# GrblMainboard_-_v2_1.net
KiCad netlist of a schematic drawn in EAGLE
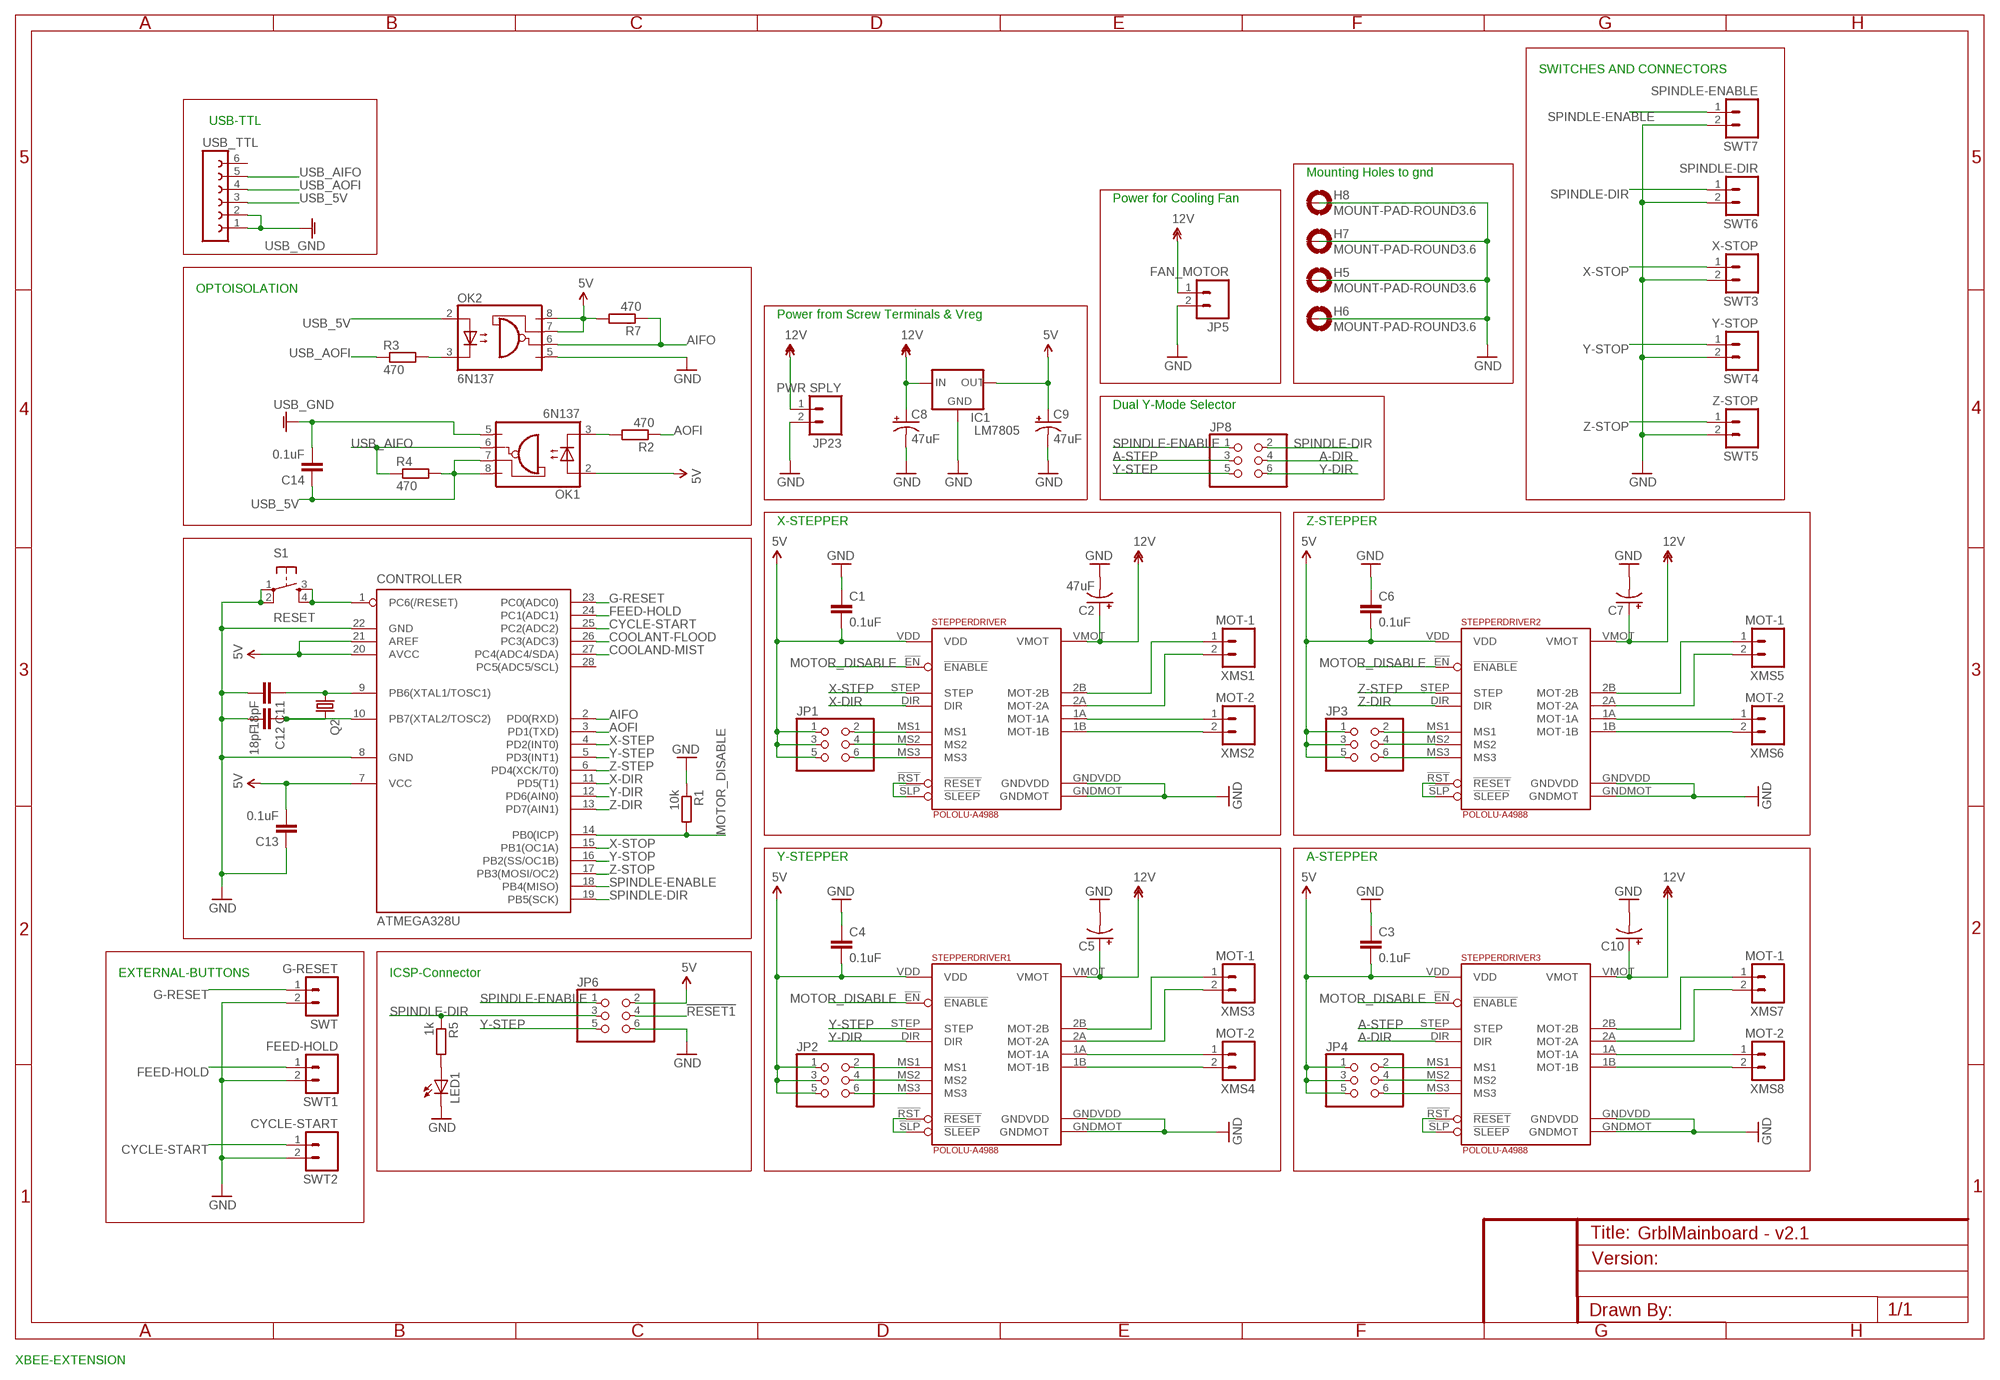
[diagram p0: schematic, sheet 1]

(export (version "E")
  (design (tool "Eeschema 10.0.6"))
  (components
    (comp (ref "ATMEGA328U")
      (value "CONTROLLER")
      (footprint "eagle-import:DIL28-3")
      (libsource (lib "eagle-import") (part "MEGA8-P"))
    )
    (comp (ref "C1")
      (value "0.1uF")
      (footprint "eagle-import:C025-025X050")
      (libsource (lib "eagle-import") (part "C-EU025-025X050"))
    )
    (comp (ref "C2")
      (value "47uF")
      (footprint "eagle-import:E2,5-6")
      (libsource (lib "eagle-import") (part "CPOL-USE2.5-6"))
    )
    (comp (ref "C3")
      (value "0.1uF")
      (footprint "eagle-import:C025-025X050")
      (libsource (lib "eagle-import") (part "C-EU025-025X050"))
    )
    (comp (ref "C4")
      (value "0.1uF")
      (footprint "eagle-import:C025-025X050")
      (libsource (lib "eagle-import") (part "C-EU025-025X050"))
    )
    (comp (ref "C5")
      (value "CPOL-USE2.5-6")
      (footprint "eagle-import:E2,5-6")
      (libsource (lib "eagle-import") (part "CPOL-USE2.5-6"))
    )
    (comp (ref "C6")
      (value "0.1uF")
      (footprint "eagle-import:C025-025X050")
      (libsource (lib "eagle-import") (part "C-EU025-025X050"))
    )
    (comp (ref "C7")
      (value "CPOL-USE2.5-6")
      (footprint "eagle-import:E2,5-6")
      (libsource (lib "eagle-import") (part "CPOL-USE2.5-6"))
    )
    (comp (ref "C8")
      (value "47uF")
      (footprint "eagle-import:E2,5-6")
      (libsource (lib "eagle-import") (part "CPOL-USE2.5-6"))
    )
    (comp (ref "C9")
      (value "47uF")
      (footprint "eagle-import:E2,5-6")
      (libsource (lib "eagle-import") (part "CPOL-USE2.5-6"))
    )
    (comp (ref "C10")
      (value "CPOL-USE2.5-6")
      (footprint "eagle-import:E2,5-6")
      (libsource (lib "eagle-import") (part "CPOL-USE2.5-6"))
    )
    (comp (ref "C11")
      (value "18pF")
      (footprint "eagle-import:CAP-PTH-SMALL2")
      (libsource (lib "eagle-import") (part "CAPPTH2"))
    )
    (comp (ref "C12")
      (value "18pF")
      (footprint "eagle-import:CAP-PTH-SMALL2")
      (libsource (lib "eagle-import") (part "CAPPTH2"))
    )
    (comp (ref "C13")
      (value "0.1uF")
      (footprint "eagle-import:CAP-PTH-SMALL2")
      (libsource (lib "eagle-import") (part "CAPPTH2"))
    )
    (comp (ref "C14")
      (value "0.1uF")
      (footprint "eagle-import:CAP-PTH-SMALL2")
      (libsource (lib "eagle-import") (part "CAPPTH2"))
    )
    (comp (ref "H5")
      (value "MOUNT-PAD-ROUND3.6")
      (footprint "eagle-import:3,6-PAD")
      (libsource (lib "eagle-import") (part "MOUNT-PAD-ROUND3.6"))
    )
    (comp (ref "H6")
      (value "MOUNT-PAD-ROUND3.6")
      (footprint "eagle-import:3,6-PAD")
      (libsource (lib "eagle-import") (part "MOUNT-PAD-ROUND3.6"))
    )
    (comp (ref "H7")
      (value "MOUNT-PAD-ROUND3.6")
      (footprint "eagle-import:3,6-PAD")
      (libsource (lib "eagle-import") (part "MOUNT-PAD-ROUND3.6"))
    )
    (comp (ref "H8")
      (value "MOUNT-PAD-ROUND3.6")
      (footprint "eagle-import:3,6-PAD")
      (libsource (lib "eagle-import") (part "MOUNT-PAD-ROUND3.6"))
    )
    (comp (ref "IC1")
      (value "LM7805")
      (footprint "eagle-import:78XXL-CUSTOM")
      (libsource (lib "eagle-import") (part "V_REG_78XX"))
    )
    (comp (ref "JP1")
      (value "PINHD-2X3")
      (footprint "eagle-import:2X03")
      (libsource (lib "eagle-import") (part "PINHD-2X3"))
    )
    (comp (ref "JP2")
      (value "PINHD-2X3")
      (footprint "eagle-import:2X03")
      (libsource (lib "eagle-import") (part "PINHD-2X3"))
    )
    (comp (ref "JP3")
      (value "PINHD-2X3")
      (footprint "eagle-import:2X03")
      (libsource (lib "eagle-import") (part "PINHD-2X3"))
    )
    (comp (ref "JP4")
      (value "PINHD-2X3")
      (footprint "eagle-import:2X03")
      (libsource (lib "eagle-import") (part "PINHD-2X3"))
    )
    (comp (ref "JP5")
      (value "FAN_MOTOR")
      (footprint "eagle-import:SCREWTERMINAL-5MM-2")
      (libsource (lib "eagle-import") (part "M025MM"))
    )
    (comp (ref "JP6")
      (value "PINHD-2X3")
      (footprint "eagle-import:2X03")
      (libsource (lib "eagle-import") (part "PINHD-2X3"))
    )
    (comp (ref "JP8")
      (value "PINHD-2X3")
      (footprint "eagle-import:2X03")
      (libsource (lib "eagle-import") (part "PINHD-2X3"))
    )
    (comp (ref "JP23")
      (value "PWR SPLY")
      (footprint "eagle-import:SCREWTERMINAL-5MM-2")
      (libsource (lib "eagle-import") (part "M025MM"))
    )
    (comp (ref "LED1")
      (value "LED5MM")
      (footprint "eagle-import:LED5MM")
      (libsource (lib "eagle-import") (part "LED5MM"))
    )
    (comp (ref "OK1")
      (value "6N137")
      (footprint "eagle-import:DIL08")
      (libsource (lib "eagle-import") (part "6N137"))
    )
    (comp (ref "OK2")
      (value "6N137")
      (footprint "eagle-import:DIL08")
      (libsource (lib "eagle-import") (part "6N137"))
    )
    (comp (ref "Q2")
      (value "CRYSTALHC49S")
      (footprint "eagle-import:HC49_S")
      (libsource (lib "eagle-import") (part "CRYSTALHC49S"))
    )
    (comp (ref "R1")
      (value "10k")
      (footprint "eagle-import:0207_10")
      (libsource (lib "eagle-import") (part "R-EU_0207/10"))
    )
    (comp (ref "R2")
      (value "470")
      (footprint "eagle-import:0207_12")
      (libsource (lib "eagle-import") (part "R-EU_0207/12"))
    )
    (comp (ref "R3")
      (value "470")
      (footprint "eagle-import:0207_12")
      (libsource (lib "eagle-import") (part "R-EU_0207/12"))
    )
    (comp (ref "R4")
      (value "470")
      (footprint "eagle-import:0207_12")
      (libsource (lib "eagle-import") (part "R-EU_0207/12"))
    )
    (comp (ref "R5")
      (value "1k")
      (footprint "eagle-import:0207_10")
      (libsource (lib "eagle-import") (part "R-EU_0207/10"))
    )
    (comp (ref "R7")
      (value "470")
      (footprint "eagle-import:0207_12")
      (libsource (lib "eagle-import") (part "R-EU_0207/12"))
    )
    (comp (ref "S1")
      (value "RESET")
      (footprint "eagle-import:TACTILE-PTH")
      (libsource (lib "eagle-import") (part "TAC_SWITCHPTH"))
    )
    (comp (ref "STEPPERDRIVER")
      (value "POLOLU-A4988")
      (footprint "eagle-import:POLOLU-ALLEGRO-PTH")
      (libsource (lib "eagle-import") (part "POLOLU-ALLEGRO"))
    )
    (comp (ref "STEPPERDRIVER1")
      (value "POLOLU-A4988")
      (footprint "eagle-import:POLOLU-ALLEGRO-PTH")
      (libsource (lib "eagle-import") (part "POLOLU-ALLEGRO"))
    )
    (comp (ref "STEPPERDRIVER2")
      (value "POLOLU-A4988")
      (footprint "eagle-import:POLOLU-ALLEGRO-PTH")
      (libsource (lib "eagle-import") (part "POLOLU-ALLEGRO"))
    )
    (comp (ref "STEPPERDRIVER3")
      (value "POLOLU-A4988")
      (footprint "eagle-import:POLOLU-ALLEGRO-PTH")
      (libsource (lib "eagle-import") (part "POLOLU-ALLEGRO"))
    )
    (comp (ref "SWT")
      (value "G-RESET")
      (footprint "eagle-import:SCREWTERMINAL-5MM-2")
      (libsource (lib "eagle-import") (part "M025MM"))
    )
    (comp (ref "SWT1")
      (value "FEED-HOLD")
      (footprint "eagle-import:SCREWTERMINAL-5MM-2")
      (libsource (lib "eagle-import") (part "M025MM"))
    )
    (comp (ref "SWT2")
      (value "CYCLE-START")
      (footprint "eagle-import:SCREWTERMINAL-5MM-2")
      (libsource (lib "eagle-import") (part "M025MM"))
    )
    (comp (ref "SWT3")
      (value "X-STOP")
      (footprint "eagle-import:SCREWTERMINAL-5MM-2")
      (libsource (lib "eagle-import") (part "M025MM"))
    )
    (comp (ref "SWT4")
      (value "Y-STOP")
      (footprint "eagle-import:SCREWTERMINAL-5MM-2")
      (libsource (lib "eagle-import") (part "M025MM"))
    )
    (comp (ref "SWT5")
      (value "Z-STOP")
      (footprint "eagle-import:SCREWTERMINAL-5MM-2")
      (libsource (lib "eagle-import") (part "M025MM"))
    )
    (comp (ref "SWT6")
      (value "SPINDLE-DIR")
      (footprint "eagle-import:SCREWTERMINAL-5MM-2")
      (libsource (lib "eagle-import") (part "M025MM"))
    )
    (comp (ref "SWT7")
      (value "SPINDLE-ENABLE")
      (footprint "eagle-import:SCREWTERMINAL-5MM-2")
      (libsource (lib "eagle-import") (part "M025MM"))
    )
    (comp (ref "USB_TTL")
      (value "FE06-1")
      (footprint "eagle-import:FE06")
      (libsource (lib "eagle-import") (part "FE06-1"))
    )
    (comp (ref "XMS1")
      (value "MOT-1")
      (footprint "eagle-import:SCREWTERMINAL-5MM-2")
      (libsource (lib "eagle-import") (part "M025MM"))
    )
    (comp (ref "XMS2")
      (value "MOT-2")
      (footprint "eagle-import:SCREWTERMINAL-5MM-2")
      (libsource (lib "eagle-import") (part "M025MM"))
    )
    (comp (ref "XMS3")
      (value "MOT-1")
      (footprint "eagle-import:SCREWTERMINAL-5MM-2")
      (libsource (lib "eagle-import") (part "M025MM"))
    )
    (comp (ref "XMS4")
      (value "MOT-2")
      (footprint "eagle-import:SCREWTERMINAL-5MM-2")
      (libsource (lib "eagle-import") (part "M025MM"))
    )
    (comp (ref "XMS5")
      (value "MOT-1")
      (footprint "eagle-import:SCREWTERMINAL-5MM-2")
      (libsource (lib "eagle-import") (part "M025MM"))
    )
    (comp (ref "XMS6")
      (value "MOT-2")
      (footprint "eagle-import:SCREWTERMINAL-5MM-2")
      (libsource (lib "eagle-import") (part "M025MM"))
    )
    (comp (ref "XMS7")
      (value "MOT-1")
      (footprint "eagle-import:SCREWTERMINAL-5MM-2")
      (libsource (lib "eagle-import") (part "M025MM"))
    )
    (comp (ref "XMS8")
      (value "MOT-2")
      (footprint "eagle-import:SCREWTERMINAL-5MM-2")
      (libsource (lib "eagle-import") (part "M025MM"))
    )
  )
  (nets
    (net (code "1") (name "/A-DIR") (class "Default")
      (node (ref "JP8") (pin "4") (pinfunction "4_4") (pintype "passive"))
      (node (ref "STEPPERDRIVER3") (pin "DIR") (pinfunction "DIR_DIR") (pintype "bidirectional"))
    )
    (net (code "2") (name "/A-STEP") (class "Default")
      (node (ref "JP8") (pin "3") (pinfunction "3_3") (pintype "passive"))
      (node (ref "STEPPERDRIVER3") (pin "STEP") (pinfunction "STEP_STEP") (pintype "bidirectional"))
    )
    (net (code "3") (name "/AIFO") (class "Default")
      (node (ref "ATMEGA328U") (pin "2") (pinfunction "PD0(RXD)_2") (pintype "bidirectional"))
      (node (ref "OK2") (pin "6") (pinfunction "VO_6") (pintype "passive"))
      (node (ref "R7") (pin "1") (pinfunction "1_1") (pintype "passive"))
    )
    (net (code "4") (name "/AOFI") (class "Default")
      (node (ref "ATMEGA328U") (pin "3") (pinfunction "PD1(TXD)_3") (pintype "bidirectional"))
      (node (ref "R2") (pin "1") (pinfunction "1_1") (pintype "passive"))
    )
    (net (code "5") (name "/COOLAND-MIST") (class "Default")
      (node (ref "ATMEGA328U") (pin "27") (pinfunction "PC4(ADC4/SDA)_27") (pintype "bidirectional"))
    )
    (net (code "6") (name "/COOLANT-FLOOD") (class "Default")
      (node (ref "ATMEGA328U") (pin "26") (pinfunction "PC3(ADC3)_26") (pintype "bidirectional"))
    )
    (net (code "7") (name "/CYCLE-START") (class "Default")
      (node (ref "ATMEGA328U") (pin "25") (pinfunction "PC2(ADC2)_25") (pintype "bidirectional"))
      (node (ref "SWT2") (pin "1") (pinfunction "1_1") (pintype "passive"))
    )
    (net (code "8") (name "/FEED-HOLD") (class "Default")
      (node (ref "ATMEGA328U") (pin "24") (pinfunction "PC1(ADC1)_24") (pintype "bidirectional"))
      (node (ref "SWT1") (pin "1") (pinfunction "1_1") (pintype "passive"))
    )
    (net (code "9") (name "/G-RESET") (class "Default")
      (node (ref "ATMEGA328U") (pin "23") (pinfunction "PC0(ADC0)_23") (pintype "bidirectional"))
      (node (ref "SWT") (pin "1") (pinfunction "1_1") (pintype "passive"))
    )
    (net (code "10") (name "/MOTOR_DISABLE") (class "Default")
      (node (ref "ATMEGA328U") (pin "14") (pinfunction "PB0(ICP)_14") (pintype "bidirectional"))
      (node (ref "R1") (pin "2") (pinfunction "2_2") (pintype "passive"))
      (node (ref "STEPPERDRIVER") (pin "!EN") (pinfunction "~{ENABLE}_!EN") (pintype "input"))
      (node (ref "STEPPERDRIVER1") (pin "!EN") (pinfunction "~{ENABLE}_!EN") (pintype "input"))
      (node (ref "STEPPERDRIVER2") (pin "!EN") (pinfunction "~{ENABLE}_!EN") (pintype "input"))
      (node (ref "STEPPERDRIVER3") (pin "!EN") (pinfunction "~{ENABLE}_!EN") (pintype "input"))
    )
    (net (code "11") (name "/SPINDLE-DIR") (class "Default")
      (node (ref "ATMEGA328U") (pin "19") (pinfunction "PB5(SCK)_19") (pintype "bidirectional"))
      (node (ref "JP6") (pin "3") (pinfunction "3_3") (pintype "passive"))
      (node (ref "JP8") (pin "2") (pinfunction "2_2") (pintype "passive"))
      (node (ref "R5") (pin "1") (pinfunction "1_1") (pintype "passive"))
      (node (ref "SWT6") (pin "1") (pinfunction "1_1") (pintype "passive"))
    )
    (net (code "12") (name "/SPINDLE-ENABLE") (class "Default")
      (node (ref "ATMEGA328U") (pin "18") (pinfunction "PB4(MISO)_18") (pintype "bidirectional"))
      (node (ref "JP6") (pin "1") (pinfunction "1_1") (pintype "passive"))
      (node (ref "JP8") (pin "1") (pinfunction "1_1") (pintype "passive"))
      (node (ref "SWT7") (pin "1") (pinfunction "1_1") (pintype "passive"))
    )
    (net (code "13") (name "/USB_5V") (class "Default")
      (node (ref "C14") (pin "1") (pinfunction "1_1") (pintype "passive"))
      (node (ref "OK1") (pin "7") (pinfunction "VE_7") (pintype "passive"))
      (node (ref "OK1") (pin "8") (pinfunction "VCC_8") (pintype "passive"))
      (node (ref "OK2") (pin "2") (pinfunction "A_2") (pintype "passive"))
      (node (ref "R4") (pin "2") (pinfunction "2_2") (pintype "passive"))
      (node (ref "USB_TTL") (pin "3") (pinfunction "3_3") (pintype "passive"))
    )
    (net (code "14") (name "/USB_AIFO") (class "Default")
      (node (ref "OK1") (pin "6") (pinfunction "VO_6") (pintype "passive"))
      (node (ref "R4") (pin "1") (pinfunction "1_1") (pintype "passive"))
      (node (ref "USB_TTL") (pin "5") (pinfunction "5_5") (pintype "passive"))
    )
    (net (code "15") (name "/USB_AOFI") (class "Default")
      (node (ref "R3") (pin "1") (pinfunction "1_1") (pintype "passive"))
      (node (ref "USB_TTL") (pin "4") (pinfunction "4_4") (pintype "passive"))
    )
    (net (code "16") (name "/X-DIR") (class "Default")
      (node (ref "ATMEGA328U") (pin "11") (pinfunction "PD5(T1)_11") (pintype "bidirectional"))
      (node (ref "STEPPERDRIVER") (pin "DIR") (pinfunction "DIR_DIR") (pintype "bidirectional"))
    )
    (net (code "17") (name "/X-STEP") (class "Default")
      (node (ref "ATMEGA328U") (pin "4") (pinfunction "PD2(INT0)_4") (pintype "bidirectional"))
      (node (ref "STEPPERDRIVER") (pin "STEP") (pinfunction "STEP_STEP") (pintype "bidirectional"))
    )
    (net (code "18") (name "/X-STOP") (class "Default")
      (node (ref "ATMEGA328U") (pin "15") (pinfunction "PB1(OC1A)_15") (pintype "bidirectional"))
      (node (ref "SWT3") (pin "1") (pinfunction "1_1") (pintype "passive"))
    )
    (net (code "19") (name "/Y-DIR") (class "Default")
      (node (ref "ATMEGA328U") (pin "12") (pinfunction "PD6(AIN0)_12") (pintype "bidirectional"))
      (node (ref "JP8") (pin "6") (pinfunction "6_6") (pintype "passive"))
      (node (ref "STEPPERDRIVER1") (pin "DIR") (pinfunction "DIR_DIR") (pintype "bidirectional"))
    )
    (net (code "20") (name "/Y-STEP") (class "Default")
      (node (ref "ATMEGA328U") (pin "5") (pinfunction "PD3(INT1)_5") (pintype "bidirectional"))
      (node (ref "JP6") (pin "5") (pinfunction "5_5") (pintype "passive"))
      (node (ref "JP8") (pin "5") (pinfunction "5_5") (pintype "passive"))
      (node (ref "STEPPERDRIVER1") (pin "STEP") (pinfunction "STEP_STEP") (pintype "bidirectional"))
    )
    (net (code "21") (name "/Y-STOP") (class "Default")
      (node (ref "ATMEGA328U") (pin "16") (pinfunction "PB2(SS/OC1B)_16") (pintype "bidirectional"))
      (node (ref "SWT4") (pin "1") (pinfunction "1_1") (pintype "passive"))
    )
    (net (code "22") (name "/Z-DIR") (class "Default")
      (node (ref "ATMEGA328U") (pin "13") (pinfunction "PD7(AIN1)_13") (pintype "bidirectional"))
      (node (ref "STEPPERDRIVER2") (pin "DIR") (pinfunction "DIR_DIR") (pintype "bidirectional"))
    )
    (net (code "23") (name "/Z-STEP") (class "Default")
      (node (ref "ATMEGA328U") (pin "6") (pinfunction "PD4(XCK/T0)_6") (pintype "bidirectional"))
      (node (ref "STEPPERDRIVER2") (pin "STEP") (pinfunction "STEP_STEP") (pintype "bidirectional"))
    )
    (net (code "24") (name "/Z-STOP") (class "Default")
      (node (ref "ATMEGA328U") (pin "17") (pinfunction "PB3(MOSI/OC2)_17") (pintype "bidirectional"))
      (node (ref "SWT5") (pin "1") (pinfunction "1_1") (pintype "passive"))
    )
    (net (code "25") (name "/~{RESET1}") (class "Default")
      (node (ref "ATMEGA328U") (pin "1") (pinfunction "PC6(/RESET)_1") (pintype "bidirectional"))
      (node (ref "JP6") (pin "4") (pinfunction "4_4") (pintype "passive"))
      (node (ref "S1") (pin "3") (pinfunction "3_3") (pintype "passive"))
      (node (ref "S1") (pin "4") (pinfunction "4_4") (pintype "passive"))
    )
    (net (code "26") (name "5V") (class "Default")
      (node (ref "ATMEGA328U") (pin "20") (pinfunction "AVCC_20") (pintype "power_in"))
      (node (ref "ATMEGA328U") (pin "21") (pinfunction "AREF_21") (pintype "passive"))
      (node (ref "ATMEGA328U") (pin "7") (pinfunction "VCC_7") (pintype "power_in"))
      (node (ref "C1") (pin "2") (pinfunction "2_2") (pintype "passive"))
      (node (ref "C13") (pin "2") (pinfunction "2_2") (pintype "passive"))
      (node (ref "C3") (pin "2") (pinfunction "2_2") (pintype "passive"))
      (node (ref "C4") (pin "2") (pinfunction "2_2") (pintype "passive"))
      (node (ref "C6") (pin "2") (pinfunction "2_2") (pintype "passive"))
      (node (ref "C9") (pin "+") (pinfunction "+_+") (pintype "passive"))
      (node (ref "IC1") (pin "OUT") (pinfunction "OUT_OUT") (pintype "output"))
      (node (ref "JP1") (pin "1") (pinfunction "1_1") (pintype "passive"))
      (node (ref "JP1") (pin "3") (pinfunction "3_3") (pintype "passive"))
      (node (ref "JP1") (pin "5") (pinfunction "5_5") (pintype "passive"))
      (node (ref "JP2") (pin "1") (pinfunction "1_1") (pintype "passive"))
      (node (ref "JP2") (pin "3") (pinfunction "3_3") (pintype "passive"))
      (node (ref "JP2") (pin "5") (pinfunction "5_5") (pintype "passive"))
      (node (ref "JP3") (pin "1") (pinfunction "1_1") (pintype "passive"))
      (node (ref "JP3") (pin "3") (pinfunction "3_3") (pintype "passive"))
      (node (ref "JP3") (pin "5") (pinfunction "5_5") (pintype "passive"))
      (node (ref "JP4") (pin "1") (pinfunction "1_1") (pintype "passive"))
      (node (ref "JP4") (pin "3") (pinfunction "3_3") (pintype "passive"))
      (node (ref "JP4") (pin "5") (pinfunction "5_5") (pintype "passive"))
      (node (ref "JP6") (pin "2") (pinfunction "2_2") (pintype "passive"))
      (node (ref "OK1") (pin "2") (pinfunction "A_2") (pintype "passive"))
      (node (ref "OK2") (pin "7") (pinfunction "VE_7") (pintype "passive"))
      (node (ref "OK2") (pin "8") (pinfunction "VCC_8") (pintype "passive"))
      (node (ref "R7") (pin "2") (pinfunction "2_2") (pintype "passive"))
      (node (ref "STEPPERDRIVER") (pin "VDD") (pinfunction "VDD_VDD") (pintype "power_in"))
      (node (ref "STEPPERDRIVER1") (pin "VDD") (pinfunction "VDD_VDD") (pintype "power_in"))
      (node (ref "STEPPERDRIVER2") (pin "VDD") (pinfunction "VDD_VDD") (pintype "power_in"))
      (node (ref "STEPPERDRIVER3") (pin "VDD") (pinfunction "VDD_VDD") (pintype "power_in"))
    )
    (net (code "27") (name "12V") (class "Default")
      (node (ref "C10") (pin "+") (pinfunction "+_+") (pintype "passive"))
      (node (ref "C2") (pin "+") (pinfunction "+_+") (pintype "passive"))
      (node (ref "C5") (pin "+") (pinfunction "+_+") (pintype "passive"))
      (node (ref "C7") (pin "+") (pinfunction "+_+") (pintype "passive"))
      (node (ref "C8") (pin "+") (pinfunction "+_+") (pintype "passive"))
      (node (ref "IC1") (pin "IN") (pinfunction "IN_IN") (pintype "input"))
      (node (ref "JP23") (pin "1") (pinfunction "1_1") (pintype "passive"))
      (node (ref "JP5") (pin "1") (pinfunction "1_1") (pintype "passive"))
      (node (ref "STEPPERDRIVER") (pin "VMOT") (pinfunction "VMOT_VMOT") (pintype "power_in"))
      (node (ref "STEPPERDRIVER1") (pin "VMOT") (pinfunction "VMOT_VMOT") (pintype "power_in"))
      (node (ref "STEPPERDRIVER2") (pin "VMOT") (pinfunction "VMOT_VMOT") (pintype "power_in"))
      (node (ref "STEPPERDRIVER3") (pin "VMOT") (pinfunction "VMOT_VMOT") (pintype "power_in"))
    )
    (net (code "28") (name "GND") (class "Default")
      (node (ref "ATMEGA328U") (pin "22") (pinfunction "GND_22") (pintype "power_in"))
      (node (ref "ATMEGA328U") (pin "8") (pinfunction "GND_8") (pintype "power_in"))
      (node (ref "C1") (pin "1") (pinfunction "1_1") (pintype "passive"))
      (node (ref "C10") (pin "-") (pinfunction "-_-") (pintype "passive"))
      (node (ref "C11") (pin "2") (pinfunction "2_2") (pintype "passive"))
      (node (ref "C12") (pin "2") (pinfunction "2_2") (pintype "passive"))
      (node (ref "C13") (pin "1") (pinfunction "1_1") (pintype "passive"))
      (node (ref "C2") (pin "-") (pinfunction "-_-") (pintype "passive"))
      (node (ref "C3") (pin "1") (pinfunction "1_1") (pintype "passive"))
      (node (ref "C4") (pin "1") (pinfunction "1_1") (pintype "passive"))
      (node (ref "C5") (pin "-") (pinfunction "-_-") (pintype "passive"))
      (node (ref "C6") (pin "1") (pinfunction "1_1") (pintype "passive"))
      (node (ref "C7") (pin "-") (pinfunction "-_-") (pintype "passive"))
      (node (ref "C8") (pin "-") (pinfunction "-_-") (pintype "passive"))
      (node (ref "C9") (pin "-") (pinfunction "-_-") (pintype "passive"))
      (node (ref "IC1") (pin "GND") (pinfunction "GND_GND") (pintype "input"))
      (node (ref "JP23") (pin "2") (pinfunction "2_2") (pintype "passive"))
      (node (ref "JP5") (pin "2") (pinfunction "2_2") (pintype "passive"))
      (node (ref "JP6") (pin "6") (pinfunction "6_6") (pintype "passive"))
      (node (ref "LED1") (pin "K") (pinfunction "C_K") (pintype "passive"))
      (node (ref "OK2") (pin "5") (pinfunction "GND_5") (pintype "passive"))
      (node (ref "R1") (pin "1") (pinfunction "1_1") (pintype "passive"))
      (node (ref "S1") (pin "1") (pinfunction "1_1") (pintype "passive"))
      (node (ref "S1") (pin "2") (pinfunction "2_2") (pintype "passive"))
      (node (ref "STEPPERDRIVER") (pin "GNDMOT") (pinfunction "GNDMOT_GNDMOT") (pintype "power_in"))
      (node (ref "STEPPERDRIVER") (pin "GNDVDD") (pinfunction "GNDVDD_GNDVDD") (pintype "power_in"))
      (node (ref "STEPPERDRIVER1") (pin "GNDMOT") (pinfunction "GNDMOT_GNDMOT") (pintype "power_in"))
      (node (ref "STEPPERDRIVER1") (pin "GNDVDD") (pinfunction "GNDVDD_GNDVDD") (pintype "power_in"))
      (node (ref "STEPPERDRIVER2") (pin "GNDMOT") (pinfunction "GNDMOT_GNDMOT") (pintype "power_in"))
      (node (ref "STEPPERDRIVER2") (pin "GNDVDD") (pinfunction "GNDVDD_GNDVDD") (pintype "power_in"))
      (node (ref "STEPPERDRIVER3") (pin "GNDMOT") (pinfunction "GNDMOT_GNDMOT") (pintype "power_in"))
      (node (ref "STEPPERDRIVER3") (pin "GNDVDD") (pinfunction "GNDVDD_GNDVDD") (pintype "power_in"))
      (node (ref "SWT") (pin "2") (pinfunction "2_2") (pintype "passive"))
      (node (ref "SWT1") (pin "2") (pinfunction "2_2") (pintype "passive"))
      (node (ref "SWT2") (pin "2") (pinfunction "2_2") (pintype "passive"))
      (node (ref "SWT3") (pin "2") (pinfunction "2_2") (pintype "passive"))
      (node (ref "SWT4") (pin "2") (pinfunction "2_2") (pintype "passive"))
      (node (ref "SWT5") (pin "2") (pinfunction "2_2") (pintype "passive"))
      (node (ref "SWT6") (pin "2") (pinfunction "2_2") (pintype "passive"))
      (node (ref "SWT7") (pin "2") (pinfunction "2_2") (pintype "passive"))
    )
    (net (code "29") (name "Net-(ATMEGA328U-PB6(XTAL1{slash}TOSC1))") (class "Default")
      (node (ref "ATMEGA328U") (pin "9") (pinfunction "PB6(XTAL1/TOSC1)_9") (pintype "bidirectional"))
      (node (ref "C11") (pin "1") (pinfunction "1_1") (pintype "passive"))
      (node (ref "Q2") (pin "1") (pinfunction "1_1") (pintype "passive"))
    )
    (net (code "30") (name "Net-(ATMEGA328U-PB7(XTAL2{slash}TOSC2))") (class "Default")
      (node (ref "ATMEGA328U") (pin "10") (pinfunction "PB7(XTAL2/TOSC2)_10") (pintype "bidirectional"))
      (node (ref "C12") (pin "1") (pinfunction "1_1") (pintype "passive"))
      (node (ref "Q2") (pin "2") (pinfunction "2_2") (pintype "passive"))
    )
    (net (code "31") (name "Net-(JP1-Pad2)") (class "Default")
      (node (ref "JP1") (pin "2") (pinfunction "2_2") (pintype "passive"))
      (node (ref "STEPPERDRIVER") (pin "MS1") (pinfunction "MS1_MS1") (pintype "input"))
    )
    (net (code "32") (name "Net-(JP1-Pad4)") (class "Default")
      (node (ref "JP1") (pin "4") (pinfunction "4_4") (pintype "passive"))
      (node (ref "STEPPERDRIVER") (pin "MS2") (pinfunction "MS2_MS2") (pintype "input"))
    )
    (net (code "33") (name "Net-(JP1-Pad6)") (class "Default")
      (node (ref "JP1") (pin "6") (pinfunction "6_6") (pintype "passive"))
      (node (ref "STEPPERDRIVER") (pin "MS3") (pinfunction "MS3_MS3") (pintype "input"))
    )
    (net (code "34") (name "Net-(JP2-Pad2)") (class "Default")
      (node (ref "JP2") (pin "2") (pinfunction "2_2") (pintype "passive"))
      (node (ref "STEPPERDRIVER1") (pin "MS1") (pinfunction "MS1_MS1") (pintype "input"))
    )
    (net (code "35") (name "Net-(JP2-Pad4)") (class "Default")
      (node (ref "JP2") (pin "4") (pinfunction "4_4") (pintype "passive"))
      (node (ref "STEPPERDRIVER1") (pin "MS2") (pinfunction "MS2_MS2") (pintype "input"))
    )
    (net (code "36") (name "Net-(JP2-Pad6)") (class "Default")
      (node (ref "JP2") (pin "6") (pinfunction "6_6") (pintype "passive"))
      (node (ref "STEPPERDRIVER1") (pin "MS3") (pinfunction "MS3_MS3") (pintype "input"))
    )
    (net (code "37") (name "Net-(JP3-Pad2)") (class "Default")
      (node (ref "JP3") (pin "2") (pinfunction "2_2") (pintype "passive"))
      (node (ref "STEPPERDRIVER2") (pin "MS1") (pinfunction "MS1_MS1") (pintype "input"))
    )
    (net (code "38") (name "Net-(JP3-Pad4)") (class "Default")
      (node (ref "JP3") (pin "4") (pinfunction "4_4") (pintype "passive"))
      (node (ref "STEPPERDRIVER2") (pin "MS2") (pinfunction "MS2_MS2") (pintype "input"))
    )
    (net (code "39") (name "Net-(JP3-Pad6)") (class "Default")
      (node (ref "JP3") (pin "6") (pinfunction "6_6") (pintype "passive"))
      (node (ref "STEPPERDRIVER2") (pin "MS3") (pinfunction "MS3_MS3") (pintype "input"))
    )
    (net (code "40") (name "Net-(JP4-Pad2)") (class "Default")
      (node (ref "JP4") (pin "2") (pinfunction "2_2") (pintype "passive"))
      (node (ref "STEPPERDRIVER3") (pin "MS1") (pinfunction "MS1_MS1") (pintype "input"))
    )
    (net (code "41") (name "Net-(JP4-Pad4)") (class "Default")
      (node (ref "JP4") (pin "4") (pinfunction "4_4") (pintype "passive"))
      (node (ref "STEPPERDRIVER3") (pin "MS2") (pinfunction "MS2_MS2") (pintype "input"))
    )
    (net (code "42") (name "Net-(JP4-Pad6)") (class "Default")
      (node (ref "JP4") (pin "6") (pinfunction "6_6") (pintype "passive"))
      (node (ref "STEPPERDRIVER3") (pin "MS3") (pinfunction "MS3_MS3") (pintype "input"))
    )
    (net (code "43") (name "Net-(LED1-PadA)") (class "Default")
      (node (ref "LED1") (pin "A") (pinfunction "A_A") (pintype "passive"))
      (node (ref "R5") (pin "2") (pinfunction "2_2") (pintype "passive"))
    )
    (net (code "44") (name "Net-(OK1-C)") (class "Default")
      (node (ref "OK1") (pin "3") (pinfunction "C_3") (pintype "passive"))
      (node (ref "R2") (pin "2") (pinfunction "2_2") (pintype "passive"))
    )
    (net (code "45") (name "Net-(OK2-C)") (class "Default")
      (node (ref "OK2") (pin "3") (pinfunction "C_3") (pintype "passive"))
      (node (ref "R3") (pin "2") (pinfunction "2_2") (pintype "passive"))
    )
    (net (code "46") (name "Net-(STEPPERDRIVER-MOT-1A)") (class "Default")
      (node (ref "STEPPERDRIVER") (pin "1A") (pinfunction "MOT-1A_1A") (pintype "power_in"))
      (node (ref "XMS2") (pin "1") (pinfunction "1_1") (pintype "passive"))
    )
    (net (code "47") (name "Net-(STEPPERDRIVER-MOT-1B)") (class "Default")
      (node (ref "STEPPERDRIVER") (pin "1B") (pinfunction "MOT-1B_1B") (pintype "power_in"))
      (node (ref "XMS2") (pin "2") (pinfunction "2_2") (pintype "passive"))
    )
    (net (code "48") (name "Net-(STEPPERDRIVER-MOT-2A)") (class "Default")
      (node (ref "STEPPERDRIVER") (pin "2A") (pinfunction "MOT-2A_2A") (pintype "power_in"))
      (node (ref "XMS1") (pin "2") (pinfunction "2_2") (pintype "passive"))
    )
    (net (code "49") (name "Net-(STEPPERDRIVER-MOT-2B)") (class "Default")
      (node (ref "STEPPERDRIVER") (pin "2B") (pinfunction "MOT-2B_2B") (pintype "power_in"))
      (node (ref "XMS1") (pin "1") (pinfunction "1_1") (pintype "passive"))
    )
    (net (code "50") (name "Net-(STEPPERDRIVER-~{RESET})") (class "Default")
      (node (ref "STEPPERDRIVER") (pin "!RST") (pinfunction "~{RESET}_!RST") (pintype "input"))
      (node (ref "STEPPERDRIVER") (pin "!SLP") (pinfunction "~{SLEEP}_!SLP") (pintype "input"))
    )
    (net (code "51") (name "Net-(STEPPERDRIVER1-MOT-1A)") (class "Default")
      (node (ref "STEPPERDRIVER1") (pin "1A") (pinfunction "MOT-1A_1A") (pintype "power_in"))
      (node (ref "XMS4") (pin "1") (pinfunction "1_1") (pintype "passive"))
    )
    (net (code "52") (name "Net-(STEPPERDRIVER1-MOT-1B)") (class "Default")
      (node (ref "STEPPERDRIVER1") (pin "1B") (pinfunction "MOT-1B_1B") (pintype "power_in"))
      (node (ref "XMS4") (pin "2") (pinfunction "2_2") (pintype "passive"))
    )
    (net (code "53") (name "Net-(STEPPERDRIVER1-MOT-2A)") (class "Default")
      (node (ref "STEPPERDRIVER1") (pin "2A") (pinfunction "MOT-2A_2A") (pintype "power_in"))
      (node (ref "XMS3") (pin "2") (pinfunction "2_2") (pintype "passive"))
    )
    (net (code "54") (name "Net-(STEPPERDRIVER1-MOT-2B)") (class "Default")
      (node (ref "STEPPERDRIVER1") (pin "2B") (pinfunction "MOT-2B_2B") (pintype "power_in"))
      (node (ref "XMS3") (pin "1") (pinfunction "1_1") (pintype "passive"))
    )
    (net (code "55") (name "Net-(STEPPERDRIVER1-~{RESET})") (class "Default")
      (node (ref "STEPPERDRIVER1") (pin "!RST") (pinfunction "~{RESET}_!RST") (pintype "input"))
      (node (ref "STEPPERDRIVER1") (pin "!SLP") (pinfunction "~{SLEEP}_!SLP") (pintype "input"))
    )
    (net (code "56") (name "Net-(STEPPERDRIVER2-MOT-1A)") (class "Default")
      (node (ref "STEPPERDRIVER2") (pin "1A") (pinfunction "MOT-1A_1A") (pintype "power_in"))
      (node (ref "XMS6") (pin "1") (pinfunction "1_1") (pintype "passive"))
    )
    (net (code "57") (name "Net-(STEPPERDRIVER2-MOT-1B)") (class "Default")
      (node (ref "STEPPERDRIVER2") (pin "1B") (pinfunction "MOT-1B_1B") (pintype "power_in"))
      (node (ref "XMS6") (pin "2") (pinfunction "2_2") (pintype "passive"))
    )
    (net (code "58") (name "Net-(STEPPERDRIVER2-MOT-2A)") (class "Default")
      (node (ref "STEPPERDRIVER2") (pin "2A") (pinfunction "MOT-2A_2A") (pintype "power_in"))
      (node (ref "XMS5") (pin "2") (pinfunction "2_2") (pintype "passive"))
    )
    (net (code "59") (name "Net-(STEPPERDRIVER2-MOT-2B)") (class "Default")
      (node (ref "STEPPERDRIVER2") (pin "2B") (pinfunction "MOT-2B_2B") (pintype "power_in"))
      (node (ref "XMS5") (pin "1") (pinfunction "1_1") (pintype "passive"))
    )
    (net (code "60") (name "Net-(STEPPERDRIVER2-~{RESET})") (class "Default")
      (node (ref "STEPPERDRIVER2") (pin "!RST") (pinfunction "~{RESET}_!RST") (pintype "input"))
      (node (ref "STEPPERDRIVER2") (pin "!SLP") (pinfunction "~{SLEEP}_!SLP") (pintype "input"))
    )
    (net (code "61") (name "Net-(STEPPERDRIVER3-MOT-1A)") (class "Default")
      (node (ref "STEPPERDRIVER3") (pin "1A") (pinfunction "MOT-1A_1A") (pintype "power_in"))
      (node (ref "XMS8") (pin "1") (pinfunction "1_1") (pintype "passive"))
    )
    (net (code "62") (name "Net-(STEPPERDRIVER3-MOT-1B)") (class "Default")
      (node (ref "STEPPERDRIVER3") (pin "1B") (pinfunction "MOT-1B_1B") (pintype "power_in"))
      (node (ref "XMS8") (pin "2") (pinfunction "2_2") (pintype "passive"))
    )
    (net (code "63") (name "Net-(STEPPERDRIVER3-MOT-2A)") (class "Default")
      (node (ref "STEPPERDRIVER3") (pin "2A") (pinfunction "MOT-2A_2A") (pintype "power_in"))
      (node (ref "XMS7") (pin "2") (pinfunction "2_2") (pintype "passive"))
    )
    (net (code "64") (name "Net-(STEPPERDRIVER3-MOT-2B)") (class "Default")
      (node (ref "STEPPERDRIVER3") (pin "2B") (pinfunction "MOT-2B_2B") (pintype "power_in"))
      (node (ref "XMS7") (pin "1") (pinfunction "1_1") (pintype "passive"))
    )
    (net (code "65") (name "Net-(STEPPERDRIVER3-~{RESET})") (class "Default")
      (node (ref "STEPPERDRIVER3") (pin "!RST") (pinfunction "~{RESET}_!RST") (pintype "input"))
      (node (ref "STEPPERDRIVER3") (pin "!SLP") (pinfunction "~{SLEEP}_!SLP") (pintype "input"))
    )
    (net (code "66") (name "USB_GND") (class "Default")
      (node (ref "C14") (pin "2") (pinfunction "2_2") (pintype "passive"))
      (node (ref "OK1") (pin "5") (pinfunction "GND_5") (pintype "passive"))
      (node (ref "USB_TTL") (pin "1") (pinfunction "1_1") (pintype "passive"))
      (node (ref "USB_TTL") (pin "2") (pinfunction "2_2") (pintype "passive"))
    )
    (net (code "67") (name "unconnected-(ATMEGA328U-PC5(ADC5{slash}SCL)-Pad28)") (class "Default")
      (node (ref "ATMEGA328U") (pin "28") (pinfunction "PC5(ADC5/SCL)_28") (pintype "bidirectional"))
    )
    (net (code "68") (name "unconnected-(H5-MOUNT-PadB3,6)") (class "Default")
      (node (ref "H5") (pin "B3,6") (pinfunction "MOUNT_B3,6") (pintype "passive"))
    )
    (net (code "69") (name "unconnected-(H6-MOUNT-PadB3,6)") (class "Default")
      (node (ref "H6") (pin "B3,6") (pinfunction "MOUNT_B3,6") (pintype "passive"))
    )
    (net (code "70") (name "unconnected-(H7-MOUNT-PadB3,6)") (class "Default")
      (node (ref "H7") (pin "B3,6") (pinfunction "MOUNT_B3,6") (pintype "passive"))
    )
    (net (code "71") (name "unconnected-(H8-MOUNT-PadB3,6)") (class "Default")
      (node (ref "H8") (pin "B3,6") (pinfunction "MOUNT_B3,6") (pintype "passive"))
    )
    (net (code "72") (name "unconnected-(USB_TTL-Pad6)") (class "Default")
      (node (ref "USB_TTL") (pin "6") (pinfunction "6_6") (pintype "passive"))
    )
  )
)
